# 01_MCU.net
KiCad netlist of a schematic drawn in Altium Designer
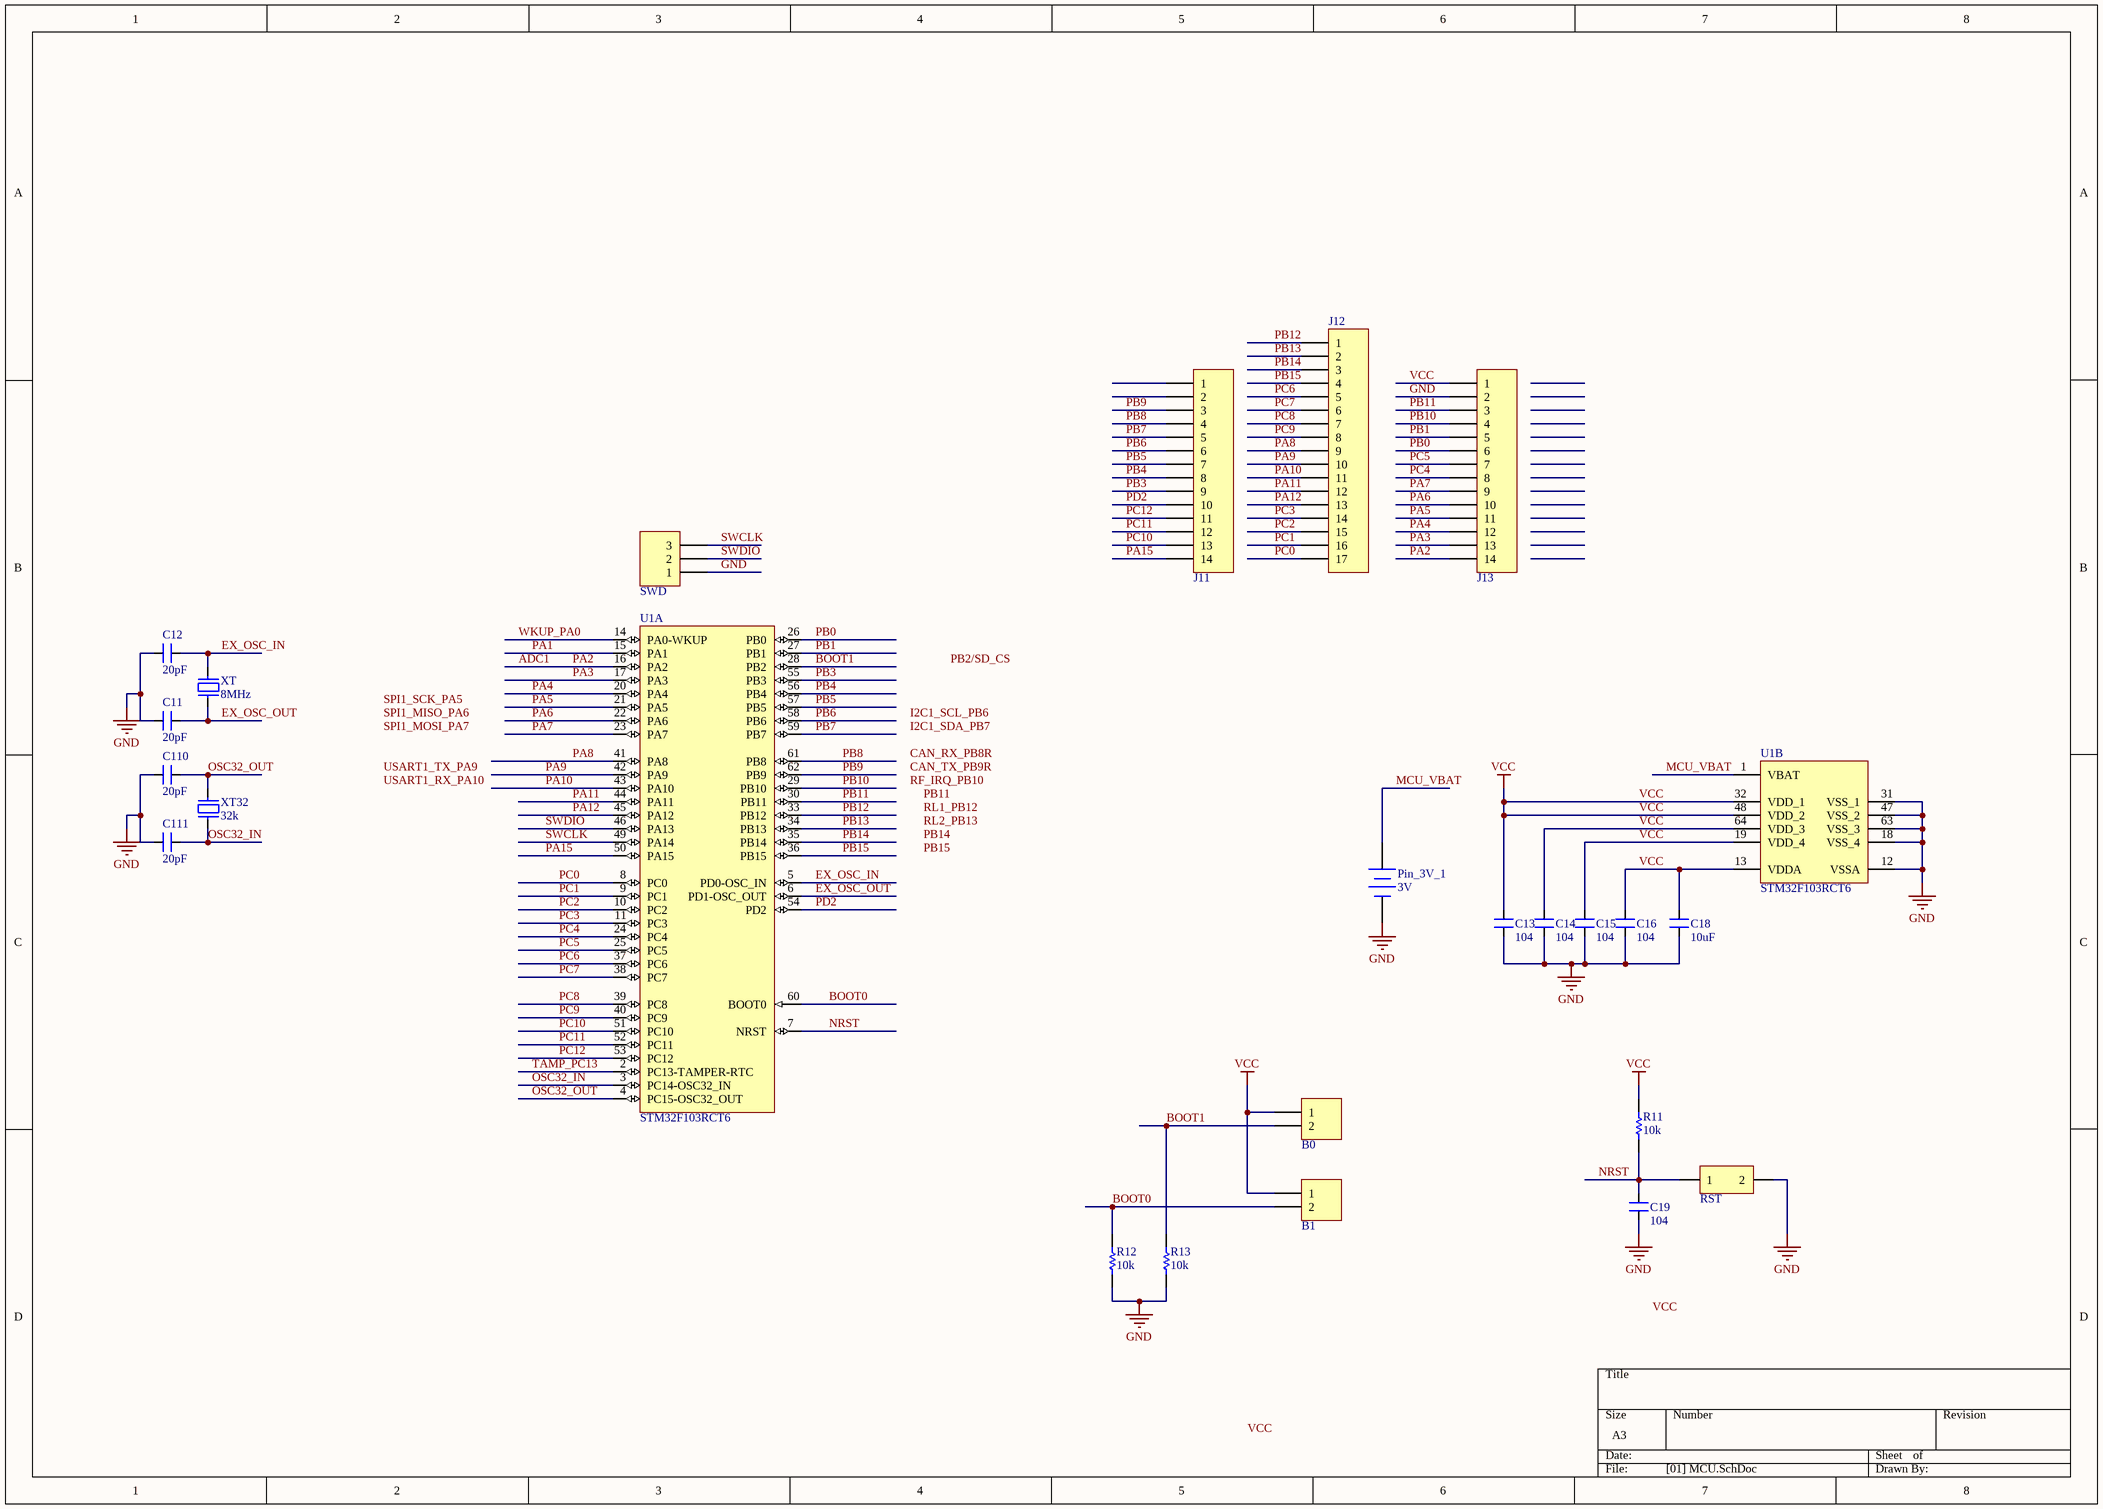
[diagram p0: [01] MCU.SchDoc]

(export (version "E")
  (design (tool "Eeschema 10.0.6"))
  (components
    (comp (ref "B0")
      (value "Header 2")
      (footprint "heromap:HDR1X2")
      (description "Header, 2-Pin")
      (fields (field (name "PUBLISHER") "Altium Limited"))
      (libsource (lib "heromap") (part "Header 2"))
    )
    (comp (ref "B1")
      (value "Header 2")
      (footprint "heromap:HDR1X2")
      (description "Header, 2-Pin")
      (fields (field (name "PUBLISHER") "Altium Limited"))
      (libsource (lib "heromap") (part "Header 2"))
    )
    (comp (ref "C11")
      (value "20pF")
      (footprint "CAPC1608N")
      (fields (field (name "Comment") "Cap_22p_0603"))
      (libsource (lib "Tuan") (part "CAP NP"))
    )
    (comp (ref "C12")
      (value "20pF")
      (footprint "CAPC1608N")
      (fields (field (name "Comment") "Cap_22p_0603"))
      (libsource (lib "Tuan") (part "CAP NP"))
    )
    (comp (ref "C13")
      (value "104")
      (footprint "CAPC1608N")
      (fields (field (name "Comment") "Cap_104_0603"))
      (libsource (lib "Tuan") (part "CAP NP"))
    )
    (comp (ref "C14")
      (value "104")
      (footprint "CAPC1608N")
      (fields (field (name "Comment") "Cap_104_0603"))
      (libsource (lib "Tuan") (part "CAP NP"))
    )
    (comp (ref "C15")
      (value "104")
      (footprint "CAPC1608N")
      (fields (field (name "Comment") "Cap_104_0603"))
      (libsource (lib "Tuan") (part "CAP NP"))
    )
    (comp (ref "C16")
      (value "104")
      (footprint "CAPC1608N")
      (fields (field (name "Comment") "Cap_104_0603"))
      (libsource (lib "Tuan") (part "CAP NP"))
    )
    (comp (ref "C18")
      (value "10uF")
      (footprint "CAPC2012N_F")
      (fields (field (name "Comment") "Cap_10uF_0805"))
      (libsource (lib "Tuan") (part "CAP NP"))
    )
    (comp (ref "C19")
      (value "104")
      (footprint "CAPC1608N")
      (fields (field (name "Comment") "Cap_104_0603"))
      (libsource (lib "Tuan") (part "CAP NP"))
    )
    (comp (ref "C110")
      (value "20pF")
      (footprint "CAPC1608N")
      (fields (field (name "Comment") "Cap_22p_0603"))
      (libsource (lib "Tuan") (part "CAP NP"))
    )
    (comp (ref "C111")
      (value "20pF")
      (footprint "CAPC1608N")
      (fields (field (name "Comment") "Cap_22p_0603"))
      (libsource (lib "Tuan") (part "CAP NP"))
    )
    (comp (ref "J11")
      (value "Header 14")
      (footprint "heromap:HDR1X14")
      (description "Header, 14-Pin")
      (fields (field (name "PUBLISHER") "Altium Limited"))
      (libsource (lib "heromap") (part "Header 14"))
    )
    (comp (ref "J12")
      (value "Header 17")
      (footprint "HDR1X17")
      (description "Header, 17-Pin")
      (fields (field (name "PUBLISHER") "Altium Limited"))
      (libsource (lib "Miscellaneous Connectors") (part "Header 17"))
    )
    (comp (ref "J13")
      (value "Header 14")
      (footprint "heromap:HDR1X14")
      (description "Header, 14-Pin")
      (fields (field (name "PUBLISHER") "Altium Limited"))
      (libsource (lib "heromap") (part "Header 14"))
    )
    (comp (ref "Pin_3V_1")
      (value "3V")
      (footprint "CR1220")
      (description "Multicell Battery")
      (fields (field (name "PUBLISHER") "Altium Limited"))
      (libsource (lib "heromap") (part "Battery"))
    )
    (comp (ref "R11")
      (value "10k")
      (footprint "RESC1608N_F")
      (fields (field (name "Comment") "Res_10k_0603"))
      (libsource (lib "Tuan") (part "Res"))
    )
    (comp (ref "R12")
      (value "10k")
      (footprint "RESC1608N_F")
      (fields (field (name "Comment") "Res_10k_0603"))
      (libsource (lib "Tuan") (part "Res"))
    )
    (comp (ref "R13")
      (value "10k")
      (footprint "RESC1608N_F")
      (fields (field (name "Comment") "Res_10k_0603"))
      (libsource (lib "Tuan") (part "Res"))
    )
    (comp (ref "RST") (value "Button") (footprint "SW") (libsource (lib "Tuan") (part "Button I")))
    (comp (ref "SWD")
      (value "Header 3")
      (footprint "heromap:HDR1X3")
      (description "Header, 3-Pin")
      (fields (field (name "PUBLISHER") "Altium Limited"))
      (libsource (lib "heromap") (part "Header 3"))
    )
    (comp (ref "U1")
      (value "STM32F103RCT6")
      (footprint "STM-LQFP64_N")
      (libsource (lib "STMicroelectronics STM32 F1") (part "STM32F103RCT6"))
    )
    (comp (ref "XT") (value "8MHz") (footprint "XT2") (libsource (lib "Tuan") (part "Crystal")))
    (comp (ref "XT32") (value "32k") (footprint "XTminiv2") (libsource (lib "Tuan") (part "Crystal")))
  )
  (nets
    (net (code "1") (name "/ADC1") (class "Default")
      (node (ref "J13") (pin "14") (pinfunction "14_14") (pintype "passive"))
      (node (ref "U1") (pin "16") (pinfunction "PA2_16") (pintype "bidirectional"))
    )
    (net (code "2") (name "/BOOT0") (class "Default")
      (node (ref "B1") (pin "2") (pinfunction "2_2") (pintype "passive"))
      (node (ref "R12") (pin "2") (pinfunction "2_2") (pintype "passive"))
      (node (ref "U1") (pin "60") (pinfunction "BOOT0_60") (pintype "input"))
    )
    (net (code "3") (name "/BOOT1") (class "Default")
      (node (ref "B0") (pin "2") (pinfunction "2_2") (pintype "passive"))
      (node (ref "R13") (pin "2") (pinfunction "2_2") (pintype "passive"))
      (node (ref "U1") (pin "28") (pinfunction "PB2_28") (pintype "bidirectional"))
    )
    (net (code "6") (name "/EX_OSC_IN") (class "Default")
      (node (ref "C12") (pin "1") (pinfunction "1_1") (pintype "passive"))
      (node (ref "U1") (pin "5") (pinfunction "PD0-OSC_IN_5") (pintype "bidirectional"))
      (node (ref "XT") (pin "2") (pinfunction "2_2") (pintype "passive"))
    )
    (net (code "7") (name "/EX_OSC_OUT") (class "Default")
      (node (ref "C11") (pin "1") (pinfunction "1_1") (pintype "passive"))
      (node (ref "U1") (pin "6") (pinfunction "PD1-OSC_OUT_6") (pintype "bidirectional"))
      (node (ref "XT") (pin "1") (pinfunction "1_1") (pintype "passive"))
    )
    (net (code "10") (name "/MCU_VBAT") (class "Default")
      (node (ref "Pin_3V_1") (pin "1") (pinfunction "+_1") (pintype "passive"))
      (node (ref "U1") (pin "1") (pinfunction "VBAT_1") (pintype "power_in"))
    )
    (net (code "11") (name "/NRST") (class "Default")
      (node (ref "C19") (pin "2") (pinfunction "2_2") (pintype "passive"))
      (node (ref "R11") (pin "1") (pinfunction "1_1") (pintype "passive"))
      (node (ref "RST") (pin "1") (pinfunction "1_1") (pintype "power_in"))
      (node (ref "U1") (pin "7") (pinfunction "NRST_7") (pintype "bidirectional"))
    )
    (net (code "12") (name "/OSC32_IN") (class "Default")
      (node (ref "C111") (pin "1") (pinfunction "1_1") (pintype "passive"))
      (node (ref "U1") (pin "3") (pinfunction "PC14-OSC32_IN_3") (pintype "bidirectional"))
      (node (ref "XT32") (pin "1") (pinfunction "1_1") (pintype "passive"))
    )
    (net (code "13") (name "/OSC32_OUT") (class "Default")
      (node (ref "C110") (pin "1") (pinfunction "1_1") (pintype "passive"))
      (node (ref "U1") (pin "4") (pinfunction "PC15-OSC32_OUT_4") (pintype "bidirectional"))
      (node (ref "XT32") (pin "2") (pinfunction "2_2") (pintype "passive"))
    )
    (net (code "14") (name "/PA1") (class "Default")
      (node (ref "U1") (pin "15") (pinfunction "PA1_15") (pintype "bidirectional"))
    )
    (net (code "15") (name "/PA3") (class "Default")
      (node (ref "J13") (pin "13") (pinfunction "13_13") (pintype "passive"))
      (node (ref "U1") (pin "17") (pinfunction "PA3_17") (pintype "bidirectional"))
    )
    (net (code "16") (name "/PA4") (class "Default")
      (node (ref "J13") (pin "12") (pinfunction "12_12") (pintype "passive"))
      (node (ref "U1") (pin "20") (pinfunction "PA4_20") (pintype "bidirectional"))
    )
    (net (code "17") (name "/PA5") (class "Default")
      (node (ref "J13") (pin "11") (pinfunction "11_11") (pintype "passive"))
      (node (ref "U1") (pin "21") (pinfunction "PA5_21") (pintype "bidirectional"))
    )
    (net (code "18") (name "/PA6") (class "Default")
      (node (ref "J13") (pin "10") (pinfunction "10_10") (pintype "passive"))
      (node (ref "U1") (pin "22") (pinfunction "PA6_22") (pintype "bidirectional"))
    )
    (net (code "19") (name "/PA7") (class "Default")
      (node (ref "J13") (pin "9") (pinfunction "9_9") (pintype "passive"))
      (node (ref "U1") (pin "23") (pinfunction "PA7_23") (pintype "bidirectional"))
    )
    (net (code "20") (name "/PA8") (class "Default")
      (node (ref "J12") (pin "9") (pinfunction "9_9") (pintype "passive"))
      (node (ref "U1") (pin "41") (pinfunction "PA8_41") (pintype "bidirectional"))
    )
    (net (code "21") (name "/PA9") (class "Default")
      (node (ref "J12") (pin "10") (pinfunction "10_10") (pintype "passive"))
      (node (ref "U1") (pin "42") (pinfunction "PA9_42") (pintype "bidirectional"))
    )
    (net (code "22") (name "/PA10") (class "Default")
      (node (ref "J12") (pin "11") (pinfunction "11_11") (pintype "passive"))
      (node (ref "U1") (pin "43") (pinfunction "PA10_43") (pintype "bidirectional"))
    )
    (net (code "23") (name "/PA11") (class "Default")
      (node (ref "J12") (pin "12") (pinfunction "12_12") (pintype "passive"))
      (node (ref "U1") (pin "44") (pinfunction "PA11_44") (pintype "bidirectional"))
    )
    (net (code "24") (name "/PA12") (class "Default")
      (node (ref "J12") (pin "13") (pinfunction "13_13") (pintype "passive"))
      (node (ref "U1") (pin "45") (pinfunction "PA12_45") (pintype "bidirectional"))
    )
    (net (code "25") (name "/PA15") (class "Default")
      (node (ref "J11") (pin "14") (pinfunction "14_14") (pintype "passive"))
      (node (ref "U1") (pin "50") (pinfunction "PA15_50") (pintype "bidirectional"))
    )
    (net (code "26") (name "/PB0") (class "Default")
      (node (ref "J13") (pin "6") (pinfunction "6_6") (pintype "passive"))
      (node (ref "U1") (pin "26") (pinfunction "PB0_26") (pintype "bidirectional"))
    )
    (net (code "27") (name "/PB1") (class "Default")
      (node (ref "J13") (pin "5") (pinfunction "5_5") (pintype "passive"))
      (node (ref "U1") (pin "27") (pinfunction "PB1_27") (pintype "bidirectional"))
    )
    (net (code "29") (name "/PB3") (class "Default")
      (node (ref "J11") (pin "9") (pinfunction "9_9") (pintype "passive"))
      (node (ref "U1") (pin "55") (pinfunction "PB3_55") (pintype "bidirectional"))
    )
    (net (code "30") (name "/PB4") (class "Default")
      (node (ref "J11") (pin "8") (pinfunction "8_8") (pintype "passive"))
      (node (ref "U1") (pin "56") (pinfunction "PB4_56") (pintype "bidirectional"))
    )
    (net (code "31") (name "/PB5") (class "Default")
      (node (ref "J11") (pin "7") (pinfunction "7_7") (pintype "passive"))
      (node (ref "U1") (pin "57") (pinfunction "PB5_57") (pintype "bidirectional"))
    )
    (net (code "32") (name "/PB6") (class "Default")
      (node (ref "J11") (pin "6") (pinfunction "6_6") (pintype "passive"))
      (node (ref "U1") (pin "58") (pinfunction "PB6_58") (pintype "bidirectional"))
    )
    (net (code "33") (name "/PB7") (class "Default")
      (node (ref "J11") (pin "5") (pinfunction "5_5") (pintype "passive"))
      (node (ref "U1") (pin "59") (pinfunction "PB7_59") (pintype "bidirectional"))
    )
    (net (code "34") (name "/PB8") (class "Default")
      (node (ref "J11") (pin "4") (pinfunction "4_4") (pintype "passive"))
      (node (ref "U1") (pin "61") (pinfunction "PB8_61") (pintype "bidirectional"))
    )
    (net (code "35") (name "/PB9") (class "Default")
      (node (ref "J11") (pin "3") (pinfunction "3_3") (pintype "passive"))
      (node (ref "U1") (pin "62") (pinfunction "PB9_62") (pintype "bidirectional"))
    )
    (net (code "36") (name "/PB10") (class "Default")
      (node (ref "J13") (pin "4") (pinfunction "4_4") (pintype "passive"))
      (node (ref "U1") (pin "29") (pinfunction "PB10_29") (pintype "bidirectional"))
    )
    (net (code "37") (name "/PB11") (class "Default")
      (node (ref "J13") (pin "3") (pinfunction "3_3") (pintype "passive"))
      (node (ref "U1") (pin "30") (pinfunction "PB11_30") (pintype "bidirectional"))
    )
    (net (code "38") (name "/PB12") (class "Default")
      (node (ref "J12") (pin "1") (pinfunction "1_1") (pintype "passive"))
      (node (ref "U1") (pin "33") (pinfunction "PB12_33") (pintype "bidirectional"))
    )
    (net (code "39") (name "/PB13") (class "Default")
      (node (ref "J12") (pin "2") (pinfunction "2_2") (pintype "passive"))
      (node (ref "U1") (pin "34") (pinfunction "PB13_34") (pintype "bidirectional"))
    )
    (net (code "40") (name "/PB14") (class "Default")
      (node (ref "J12") (pin "3") (pinfunction "3_3") (pintype "passive"))
      (node (ref "U1") (pin "35") (pinfunction "PB14_35") (pintype "bidirectional"))
    )
    (net (code "41") (name "/PB15") (class "Default")
      (node (ref "J12") (pin "4") (pinfunction "4_4") (pintype "passive"))
      (node (ref "U1") (pin "36") (pinfunction "PB15_36") (pintype "bidirectional"))
    )
    (net (code "42") (name "/PC0") (class "Default")
      (node (ref "J12") (pin "17") (pinfunction "17_17") (pintype "passive"))
      (node (ref "U1") (pin "8") (pinfunction "PC0_8") (pintype "bidirectional"))
    )
    (net (code "43") (name "/PC1") (class "Default")
      (node (ref "J12") (pin "16") (pinfunction "16_16") (pintype "passive"))
      (node (ref "U1") (pin "9") (pinfunction "PC1_9") (pintype "bidirectional"))
    )
    (net (code "44") (name "/PC2") (class "Default")
      (node (ref "J12") (pin "15") (pinfunction "15_15") (pintype "passive"))
      (node (ref "U1") (pin "10") (pinfunction "PC2_10") (pintype "bidirectional"))
    )
    (net (code "45") (name "/PC3") (class "Default")
      (node (ref "J12") (pin "14") (pinfunction "14_14") (pintype "passive"))
      (node (ref "U1") (pin "11") (pinfunction "PC3_11") (pintype "bidirectional"))
    )
    (net (code "46") (name "/PC4") (class "Default")
      (node (ref "J13") (pin "8") (pinfunction "8_8") (pintype "passive"))
      (node (ref "U1") (pin "24") (pinfunction "PC4_24") (pintype "bidirectional"))
    )
    (net (code "47") (name "/PC5") (class "Default")
      (node (ref "J13") (pin "7") (pinfunction "7_7") (pintype "passive"))
      (node (ref "U1") (pin "25") (pinfunction "PC5_25") (pintype "bidirectional"))
    )
    (net (code "48") (name "/PC6") (class "Default")
      (node (ref "J12") (pin "5") (pinfunction "5_5") (pintype "passive"))
      (node (ref "U1") (pin "37") (pinfunction "PC6_37") (pintype "bidirectional"))
    )
    (net (code "49") (name "/PC7") (class "Default")
      (node (ref "J12") (pin "6") (pinfunction "6_6") (pintype "passive"))
      (node (ref "U1") (pin "38") (pinfunction "PC7_38") (pintype "bidirectional"))
    )
    (net (code "50") (name "/PC8") (class "Default")
      (node (ref "J12") (pin "7") (pinfunction "7_7") (pintype "passive"))
      (node (ref "U1") (pin "39") (pinfunction "PC8_39") (pintype "bidirectional"))
    )
    (net (code "51") (name "/PC9") (class "Default")
      (node (ref "J12") (pin "8") (pinfunction "8_8") (pintype "passive"))
      (node (ref "U1") (pin "40") (pinfunction "PC9_40") (pintype "bidirectional"))
    )
    (net (code "52") (name "/PC10") (class "Default")
      (node (ref "J11") (pin "13") (pinfunction "13_13") (pintype "passive"))
      (node (ref "U1") (pin "51") (pinfunction "PC10_51") (pintype "bidirectional"))
    )
    (net (code "53") (name "/PC11") (class "Default")
      (node (ref "J11") (pin "12") (pinfunction "12_12") (pintype "passive"))
      (node (ref "U1") (pin "52") (pinfunction "PC11_52") (pintype "bidirectional"))
    )
    (net (code "54") (name "/PC12") (class "Default")
      (node (ref "J11") (pin "11") (pinfunction "11_11") (pintype "passive"))
      (node (ref "U1") (pin "53") (pinfunction "PC12_53") (pintype "bidirectional"))
    )
    (net (code "55") (name "/PD2") (class "Default")
      (node (ref "J11") (pin "10") (pinfunction "10_10") (pintype "passive"))
      (node (ref "U1") (pin "54") (pinfunction "PD2_54") (pintype "bidirectional"))
    )
    (net (code "62") (name "/SWCLK") (class "Default")
      (node (ref "SWD") (pin "3") (pinfunction "3_3") (pintype "passive"))
      (node (ref "U1") (pin "49") (pinfunction "PA14_49") (pintype "bidirectional"))
    )
    (net (code "63") (name "/SWDIO") (class "Default")
      (node (ref "SWD") (pin "2") (pinfunction "2_2") (pintype "passive"))
      (node (ref "U1") (pin "46") (pinfunction "PA13_46") (pintype "bidirectional"))
    )
    (net (code "64") (name "/TAMP_PC13") (class "Default")
      (node (ref "U1") (pin "2") (pinfunction "PC13-TAMPER-RTC_2") (pintype "bidirectional"))
    )
    (net (code "67") (name "/WKUP_PA0") (class "Default")
      (node (ref "U1") (pin "14") (pinfunction "PA0-WKUP_14") (pintype "bidirectional"))
    )
    (net (code "68") (name "GND") (class "Default")
      (node (ref "C11") (pin "2") (pinfunction "2_2") (pintype "passive"))
      (node (ref "C110") (pin "2") (pinfunction "2_2") (pintype "passive"))
      (node (ref "C111") (pin "2") (pinfunction "2_2") (pintype "passive"))
      (node (ref "C12") (pin "2") (pinfunction "2_2") (pintype "passive"))
      (node (ref "C13") (pin "1") (pinfunction "1_1") (pintype "passive"))
      (node (ref "C14") (pin "1") (pinfunction "1_1") (pintype "passive"))
      (node (ref "C15") (pin "1") (pinfunction "1_1") (pintype "passive"))
      (node (ref "C16") (pin "1") (pinfunction "1_1") (pintype "passive"))
      (node (ref "C18") (pin "1") (pinfunction "1_1") (pintype "passive"))
      (node (ref "C19") (pin "1") (pinfunction "1_1") (pintype "passive"))
      (node (ref "J13") (pin "2") (pinfunction "2_2") (pintype "passive"))
      (node (ref "Pin_3V_1") (pin "2") (pinfunction "-_2") (pintype "passive"))
      (node (ref "R12") (pin "1") (pinfunction "1_1") (pintype "passive"))
      (node (ref "R13") (pin "1") (pinfunction "1_1") (pintype "passive"))
      (node (ref "RST") (pin "2") (pinfunction "2_2") (pintype "power_in"))
      (node (ref "SWD") (pin "1") (pinfunction "1_1") (pintype "passive"))
      (node (ref "U1") (pin "12") (pinfunction "VSSA_12") (pintype "power_in"))
      (node (ref "U1") (pin "18") (pinfunction "VSS_4_18") (pintype "power_in"))
      (node (ref "U1") (pin "31") (pinfunction "VSS_1_31") (pintype "power_in"))
      (node (ref "U1") (pin "47") (pinfunction "VSS_2_47") (pintype "power_in"))
      (node (ref "U1") (pin "63") (pinfunction "VSS_3_63") (pintype "power_in"))
    )
    (net (code "69") (name "VCC") (class "Default")
      (node (ref "B0") (pin "1") (pinfunction "1_1") (pintype "passive"))
      (node (ref "B1") (pin "1") (pinfunction "1_1") (pintype "passive"))
      (node (ref "C13") (pin "2") (pinfunction "2_2") (pintype "passive"))
      (node (ref "C14") (pin "2") (pinfunction "2_2") (pintype "passive"))
      (node (ref "C15") (pin "2") (pinfunction "2_2") (pintype "passive"))
      (node (ref "C16") (pin "2") (pinfunction "2_2") (pintype "passive"))
      (node (ref "C18") (pin "2") (pinfunction "2_2") (pintype "passive"))
      (node (ref "J13") (pin "1") (pinfunction "1_1") (pintype "passive"))
      (node (ref "R11") (pin "2") (pinfunction "2_2") (pintype "passive"))
      (node (ref "U1") (pin "13") (pinfunction "VDDA_13") (pintype "power_in"))
      (node (ref "U1") (pin "19") (pinfunction "VDD_4_19") (pintype "power_in"))
      (node (ref "U1") (pin "32") (pinfunction "VDD_1_32") (pintype "power_in"))
      (node (ref "U1") (pin "48") (pinfunction "VDD_2_48") (pintype "power_in"))
      (node (ref "U1") (pin "64") (pinfunction "VDD_3_64") (pintype "power_in"))
    )
    (net (code "70") (name "unconnected-(J11-Pad1)") (class "Default")
      (node (ref "J11") (pin "1") (pinfunction "1_1") (pintype "passive"))
    )
    (net (code "71") (name "unconnected-(J11-Pad2)") (class "Default")
      (node (ref "J11") (pin "2") (pinfunction "2_2") (pintype "passive"))
    )
  )
)
